# torque_sensor.net
KiCad netlist of a schematic drawn in EAGLE
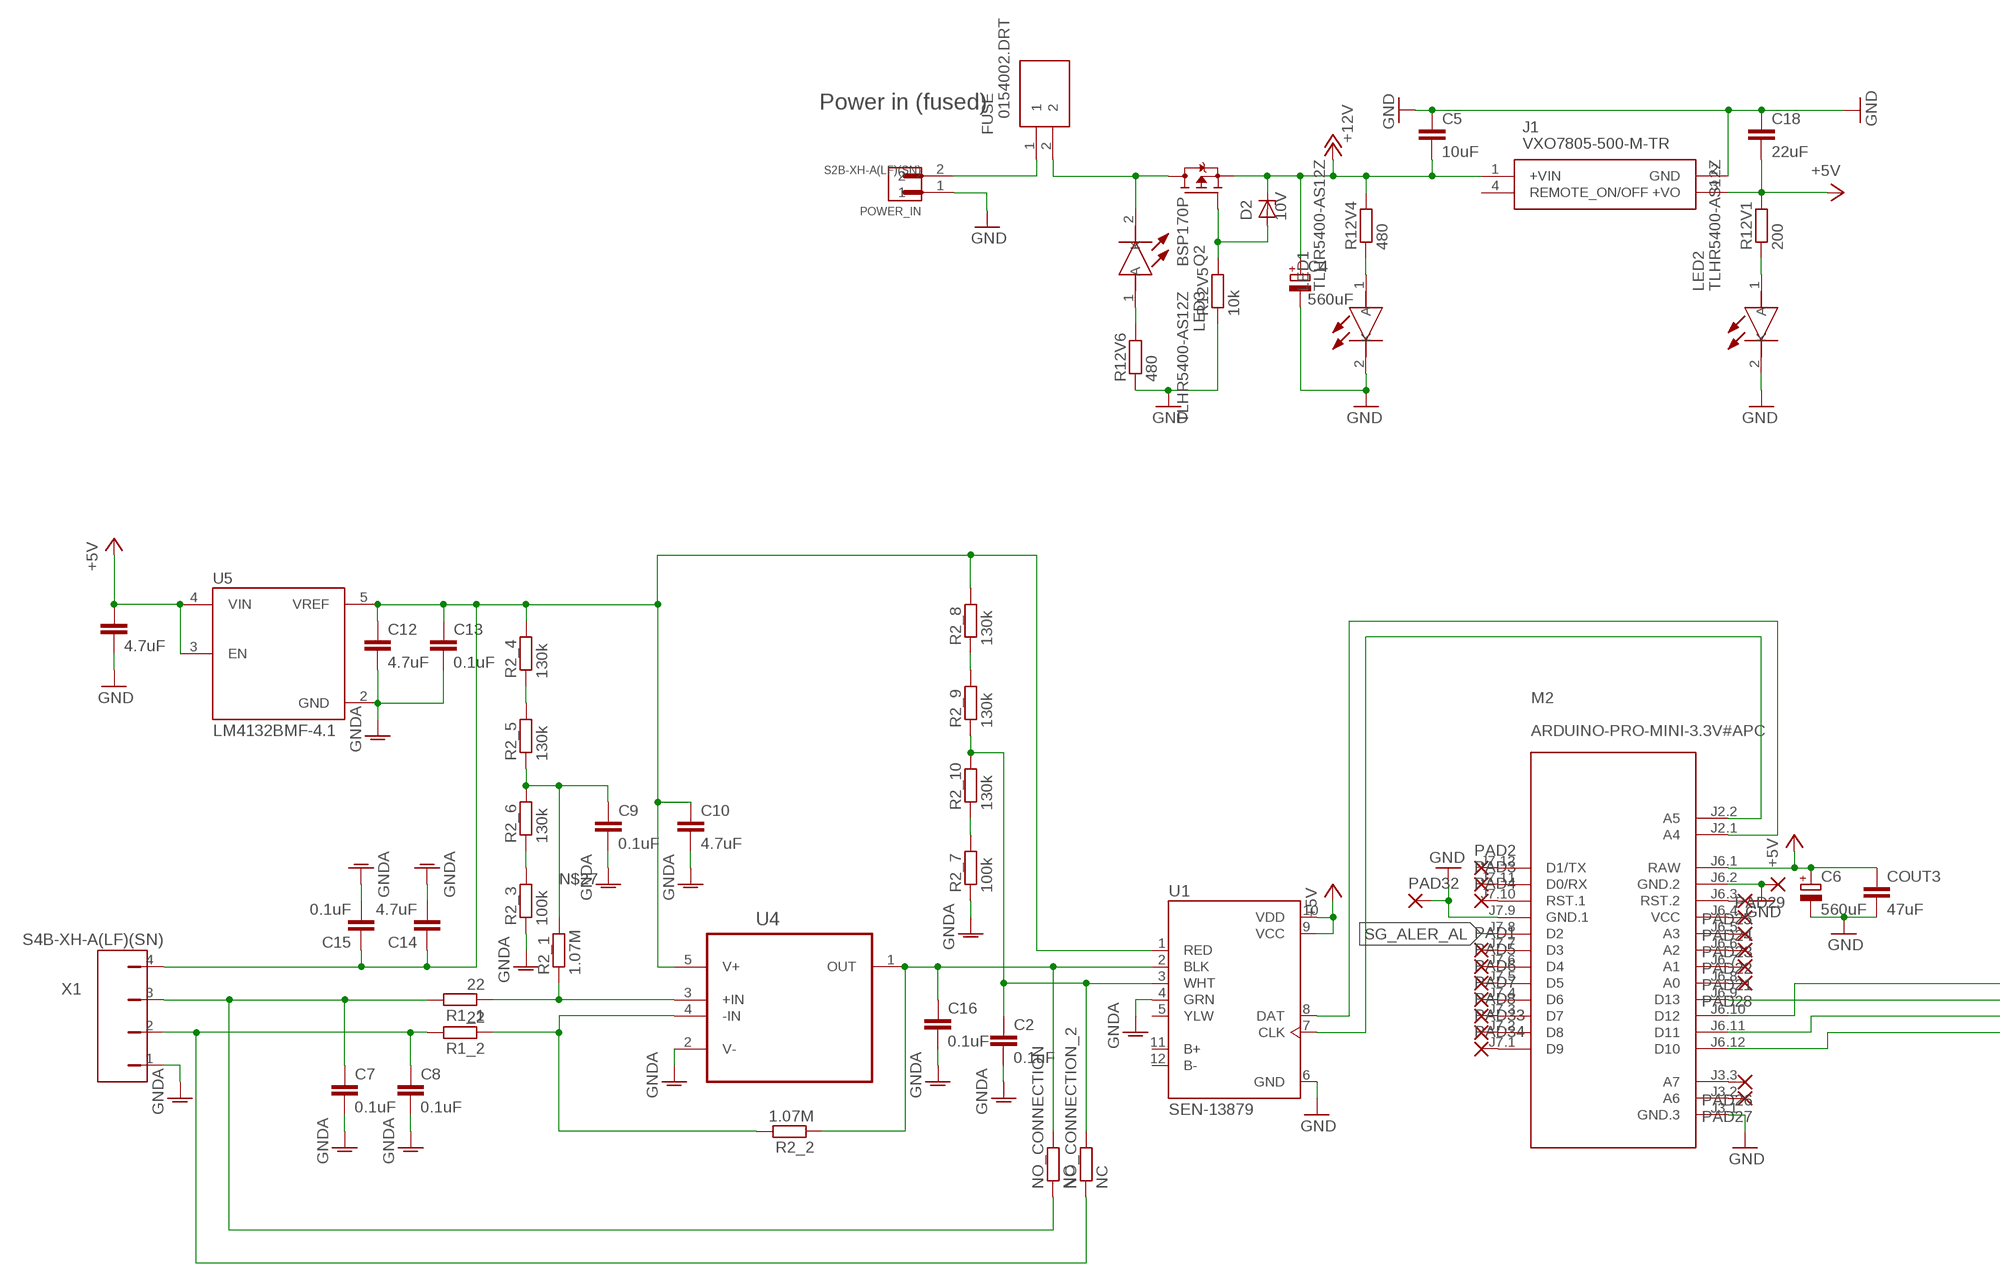
[diagram p0: schematic, sheet 1, part 1 of 2]
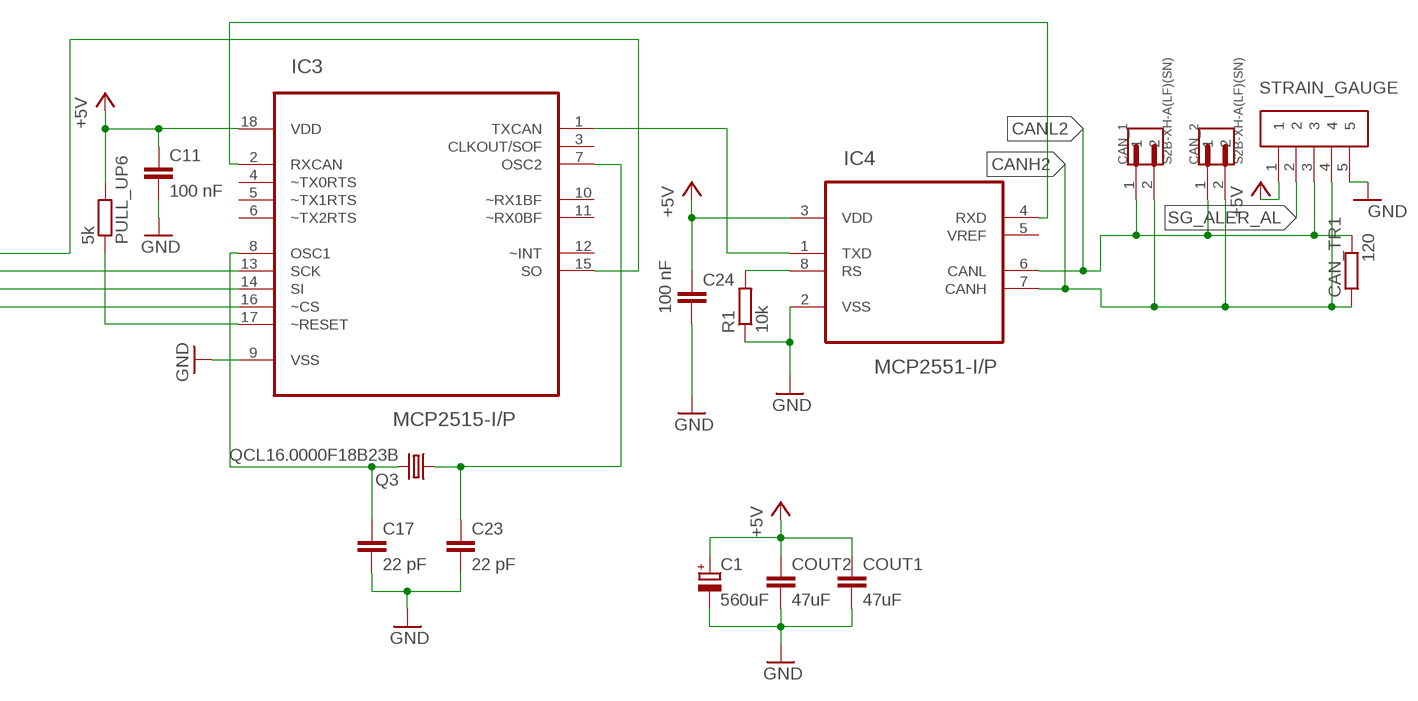
[diagram p1: schematic, sheet 1, part 2 of 2]

(export (version "E")
  (design (tool "Eeschema 10.0.6"))
  (components
    (comp (ref "C1")
      (value "560uF")
      (footprint "eagle-import:PANASONIC_F")
      (libsource (lib "eagle-import") (part "CPOL-EUF"))
    )
    (comp (ref "C2")
      (value "0.1uF")
      (footprint "eagle-import:C0805")
      (libsource (lib "eagle-import") (part "C-EUC0805"))
    )
    (comp (ref "C3")
      (value "4.7uF")
      (footprint "eagle-import:C0805")
      (libsource (lib "eagle-import") (part "C-EUC0805"))
    )
    (comp (ref "C4")
      (value "560uF")
      (footprint "eagle-import:PANASONIC_F")
      (libsource (lib "eagle-import") (part "CPOL-EUF"))
    )
    (comp (ref "C5")
      (value "10uF")
      (footprint "eagle-import:C0805")
      (libsource (lib "eagle-import") (part "C-EUC0805"))
    )
    (comp (ref "C6")
      (value "560uF")
      (footprint "eagle-import:PANASONIC_F")
      (libsource (lib "eagle-import") (part "CPOL-EUF"))
    )
    (comp (ref "C7")
      (value "0.1uF")
      (footprint "eagle-import:C0805")
      (libsource (lib "eagle-import") (part "C-EUC0805"))
    )
    (comp (ref "C8")
      (value "0.1uF")
      (footprint "eagle-import:C0805")
      (libsource (lib "eagle-import") (part "C-EUC0805"))
    )
    (comp (ref "C9")
      (value "0.1uF")
      (footprint "eagle-import:C0805")
      (libsource (lib "eagle-import") (part "C-EUC0805"))
    )
    (comp (ref "C10")
      (value "4.7uF")
      (footprint "eagle-import:C0805")
      (libsource (lib "eagle-import") (part "C-EUC0805"))
    )
    (comp (ref "C11")
      (value "100 nF")
      (footprint "eagle-import:C0805")
      (libsource (lib "eagle-import") (part "C-EUC0805"))
    )
    (comp (ref "C12")
      (value "4.7uF")
      (footprint "eagle-import:C0805")
      (libsource (lib "eagle-import") (part "C-EUC0805"))
    )
    (comp (ref "C13")
      (value "0.1uF")
      (footprint "eagle-import:C0805")
      (libsource (lib "eagle-import") (part "C-EUC0805"))
    )
    (comp (ref "C14")
      (value "4.7uF")
      (footprint "eagle-import:C0805")
      (libsource (lib "eagle-import") (part "C-EUC0805"))
    )
    (comp (ref "C15")
      (value "0.1uF")
      (footprint "eagle-import:C0805")
      (libsource (lib "eagle-import") (part "C-EUC0805"))
    )
    (comp (ref "C16")
      (value "0.1uF")
      (footprint "eagle-import:C0805")
      (libsource (lib "eagle-import") (part "C-EUC0805"))
    )
    (comp (ref "C17")
      (value "22 pF")
      (footprint "eagle-import:C0805")
      (libsource (lib "eagle-import") (part "C-EUC0805"))
    )
    (comp (ref "C18")
      (value "22uF")
      (footprint "eagle-import:C0805")
      (libsource (lib "eagle-import") (part "C-EUC0805"))
    )
    (comp (ref "C23")
      (value "22 pF")
      (footprint "eagle-import:C0805")
      (libsource (lib "eagle-import") (part "C-EUC0805"))
    )
    (comp (ref "C24")
      (value "100 nF")
      (footprint "eagle-import:C0805")
      (libsource (lib "eagle-import") (part "C-EUC0805"))
    )
    (comp (ref "CAN_1")
      (value "S2B-XH-A(LF)(SN)")
      (footprint "eagle-import:JST_S2B-XH-A(LF)(SN)")
      (fields
        (field (name "DIGI-KEY_PART_NUMBER") "455-2257-ND")
        (field (name "MF") "JST Sales")
        (field (name "MP") "S2B-XH-A_LF__SN_")
      )
      (libsource (lib "eagle-import") (part "S2B-XH-A(LF)(SN)"))
    )
    (comp (ref "CAN_2")
      (value "S2B-XH-A(LF)(SN)")
      (footprint "eagle-import:JST_S2B-XH-A(LF)(SN)")
      (fields
        (field (name "DIGI-KEY_PART_NUMBER") "455-2257-ND")
        (field (name "MF") "JST Sales")
        (field (name "MP") "S2B-XH-A_LF__SN_")
      )
      (libsource (lib "eagle-import") (part "S2B-XH-A(LF)(SN)"))
    )
    (comp (ref "CAN_TR1")
      (value "120")
      (footprint "eagle-import:R0805")
      (libsource (lib "eagle-import") (part "R-EU_R0805"))
    )
    (comp (ref "COUT1")
      (value "47uF")
      (footprint "eagle-import:C0805")
      (libsource (lib "eagle-import") (part "C-EUC0805"))
    )
    (comp (ref "COUT2")
      (value "47uF")
      (footprint "eagle-import:C0805")
      (libsource (lib "eagle-import") (part "C-EUC0805"))
    )
    (comp (ref "COUT3")
      (value "47uF")
      (footprint "eagle-import:C0805")
      (libsource (lib "eagle-import") (part "C-EUC0805"))
    )
    (comp (ref "D2")
      (value "10V")
      (footprint "eagle-import:SMB")
      (libsource (lib "eagle-import") (part "ZENER-DIODESMB"))
    )
    (comp (ref "FUSE")
      (value "0154002.DRT")
      (footprint "eagle-import:FUSM9750X381N")
      (fields (field (name "MOUSER_PART_NUMBER") "576-0154002.DRT"))
      (libsource (lib "eagle-import") (part "0154002.DRT"))
    )
    (comp (ref "IC3")
      (value "MCP2515-I/P")
      (footprint "eagle-import:DIP254P762X432-18")
      (fields (field (name "MF") "Microchip"))
      (libsource (lib "eagle-import") (part "MCP2515-I/P"))
    )
    (comp (ref "IC4")
      (value "MCP2551-I/P")
      (footprint "eagle-import:DIP254P762X432-8")
      (fields (field (name "MF") "Microchip"))
      (libsource (lib "eagle-import") (part "MCP2551-I/P"))
    )
    (comp (ref "J1")
      (value "VXO7805-500-M-TR")
      (footprint "eagle-import:VXO7805500MTR")
      (fields (field (name "MOUSER_PART_NUMBER") "490-VXO7805-500-M-TR"))
      (libsource (lib "eagle-import") (part "VXO7805-500-M-TR"))
    )
    (comp (ref "LED1")
      (value "TLHR5400-AS12Z")
      (footprint "eagle-import:TLHR5400AS12Z")
      (fields (field (name "MOUSER_PART_NUMBER") "78-TLHR5400-AS12Z"))
      (libsource (lib "eagle-import") (part "TLHR5400-AS12Z"))
    )
    (comp (ref "LED2")
      (value "TLHR5400-AS12Z")
      (footprint "eagle-import:TLHR5400AS12Z")
      (fields (field (name "MOUSER_PART_NUMBER") "78-TLHR5400-AS12Z"))
      (libsource (lib "eagle-import") (part "TLHR5400-AS12Z"))
    )
    (comp (ref "LED3")
      (value "TLHR5400-AS12Z")
      (footprint "eagle-import:TLHR5400AS12Z")
      (fields (field (name "MOUSER_PART_NUMBER") "78-TLHR5400-AS12Z"))
      (libsource (lib "eagle-import") (part "TLHR5400-AS12Z"))
    )
    (comp (ref "M2")
      (value "ARDUINO-PRO-MINI-3.3V#APC")
      (footprint "eagle-import:ARDUINO-PRO-MINI#APC")
      (libsource (lib "eagle-import") (part "ARDUINO-PRO-MINI-#APC3.3V"))
    )
    (comp (ref "NO_CONNECTION")
      (value "NC")
      (footprint "eagle-import:R0805")
      (libsource (lib "eagle-import") (part "R-EU_R0805"))
    )
    (comp (ref "NO_CONNECTION_2")
      (value "NC")
      (footprint "eagle-import:R0805")
      (libsource (lib "eagle-import") (part "R-EU_R0805"))
    )
    (comp (ref "PAD1")
      (value "SMD2")
      (footprint "eagle-import:SMD1,27-2,54")
      (libsource (lib "eagle-import") (part "SMD2"))
    )
    (comp (ref "PAD2")
      (value "SMD2")
      (footprint "eagle-import:SMD1,27-2,54")
      (libsource (lib "eagle-import") (part "SMD2"))
    )
    (comp (ref "PAD3")
      (value "SMD2")
      (footprint "eagle-import:SMD1,27-2,54")
      (libsource (lib "eagle-import") (part "SMD2"))
    )
    (comp (ref "PAD4")
      (value "SMD2")
      (footprint "eagle-import:SMD1,27-2,54")
      (libsource (lib "eagle-import") (part "SMD2"))
    )
    (comp (ref "PAD5")
      (value "SMD2")
      (footprint "eagle-import:SMD1,27-2,54")
      (libsource (lib "eagle-import") (part "SMD2"))
    )
    (comp (ref "PAD6")
      (value "SMD2")
      (footprint "eagle-import:SMD1,27-2,54")
      (libsource (lib "eagle-import") (part "SMD2"))
    )
    (comp (ref "PAD7")
      (value "SMD2")
      (footprint "eagle-import:SMD1,27-2,54")
      (libsource (lib "eagle-import") (part "SMD2"))
    )
    (comp (ref "PAD8")
      (value "SMD2")
      (footprint "eagle-import:SMD1,27-2,54")
      (libsource (lib "eagle-import") (part "SMD2"))
    )
    (comp (ref "PAD21")
      (value "SMD2")
      (footprint "eagle-import:SMD1,27-2,54")
      (libsource (lib "eagle-import") (part "SMD2"))
    )
    (comp (ref "PAD22")
      (value "SMD2")
      (footprint "eagle-import:SMD1,27-2,54")
      (libsource (lib "eagle-import") (part "SMD2"))
    )
    (comp (ref "PAD23")
      (value "SMD2")
      (footprint "eagle-import:SMD1,27-2,54")
      (libsource (lib "eagle-import") (part "SMD2"))
    )
    (comp (ref "PAD24")
      (value "SMD2")
      (footprint "eagle-import:SMD1,27-2,54")
      (libsource (lib "eagle-import") (part "SMD2"))
    )
    (comp (ref "PAD25")
      (value "SMD2")
      (footprint "eagle-import:SMD1,27-2,54")
      (libsource (lib "eagle-import") (part "SMD2"))
    )
    (comp (ref "PAD26")
      (value "SMD2")
      (footprint "eagle-import:SMD1,27-2,54")
      (libsource (lib "eagle-import") (part "SMD2"))
    )
    (comp (ref "PAD27")
      (value "SMD2")
      (footprint "eagle-import:SMD1,27-2,54")
      (libsource (lib "eagle-import") (part "SMD2"))
    )
    (comp (ref "PAD28")
      (value "SMD2")
      (footprint "eagle-import:SMD1,27-2,54")
      (libsource (lib "eagle-import") (part "SMD2"))
    )
    (comp (ref "PAD29")
      (value "SMD2")
      (footprint "eagle-import:SMD1,27-2,54")
      (libsource (lib "eagle-import") (part "SMD2"))
    )
    (comp (ref "PAD32")
      (value "SMD2")
      (footprint "eagle-import:SMD1,27-2,54")
      (libsource (lib "eagle-import") (part "SMD2"))
    )
    (comp (ref "PAD33")
      (value "SMD2")
      (footprint "eagle-import:SMD1,27-2,54")
      (libsource (lib "eagle-import") (part "SMD2"))
    )
    (comp (ref "PAD34")
      (value "SMD2")
      (footprint "eagle-import:SMD1,27-2,54")
      (libsource (lib "eagle-import") (part "SMD2"))
    )
    (comp (ref "POWER_IN")
      (value "S2B-XH-A(LF)(SN)")
      (footprint "eagle-import:JST_S2B-XH-A(LF)(SN)")
      (fields
        (field (name "DIGI-KEY_PART_NUMBER") "455-2257-ND")
        (field (name "MF") "JST Sales")
        (field (name "MP") "S2B-XH-A_LF__SN_")
      )
      (libsource (lib "eagle-import") (part "S2B-XH-A(LF)(SN)"))
    )
    (comp (ref "PULL_UP6")
      (value "5k")
      (footprint "eagle-import:R0805")
      (libsource (lib "eagle-import") (part "R-EU_R0805"))
    )
    (comp (ref "Q2")
      (value "BSP170P")
      (footprint "eagle-import:SOT223")
      (libsource (lib "eagle-import") (part "BSP170P"))
    )
    (comp (ref "Q3")
      (value "QCL16.0000F18B23B")
      (footprint "eagle-import:HC49_S")
      (libsource (lib "eagle-import") (part "CRYSTALHC49S"))
    )
    (comp (ref "R1")
      (value "10k")
      (footprint "eagle-import:R0805")
      (libsource (lib "eagle-import") (part "R-EU_R0805"))
    )
    (comp (ref "R1_1")
      (value "22")
      (footprint "eagle-import:R0805")
      (libsource (lib "eagle-import") (part "R-EU_R0805"))
    )
    (comp (ref "R1_2")
      (value "22")
      (footprint "eagle-import:R0805")
      (libsource (lib "eagle-import") (part "R-EU_R0805"))
    )
    (comp (ref "R2_1")
      (value "1.07M")
      (footprint "eagle-import:R0805")
      (libsource (lib "eagle-import") (part "R-EU_R0805"))
    )
    (comp (ref "R2_2")
      (value "1.07M")
      (footprint "eagle-import:R0805")
      (libsource (lib "eagle-import") (part "R-EU_R0805"))
    )
    (comp (ref "R2_3")
      (value "100k")
      (footprint "eagle-import:R0805")
      (libsource (lib "eagle-import") (part "R-EU_R0805"))
    )
    (comp (ref "R2_4")
      (value "130k")
      (footprint "eagle-import:R0805")
      (libsource (lib "eagle-import") (part "R-EU_R0805"))
    )
    (comp (ref "R2_5")
      (value "130k")
      (footprint "eagle-import:R0805")
      (libsource (lib "eagle-import") (part "R-EU_R0805"))
    )
    (comp (ref "R2_6")
      (value "130k")
      (footprint "eagle-import:R0805")
      (libsource (lib "eagle-import") (part "R-EU_R0805"))
    )
    (comp (ref "R2_7")
      (value "100k")
      (footprint "eagle-import:R0805")
      (libsource (lib "eagle-import") (part "R-EU_R0805"))
    )
    (comp (ref "R2_8")
      (value "130k")
      (footprint "eagle-import:R0805")
      (libsource (lib "eagle-import") (part "R-EU_R0805"))
    )
    (comp (ref "R2_9")
      (value "130k")
      (footprint "eagle-import:R0805")
      (libsource (lib "eagle-import") (part "R-EU_R0805"))
    )
    (comp (ref "R2_10")
      (value "130k")
      (footprint "eagle-import:R0805")
      (libsource (lib "eagle-import") (part "R-EU_R0805"))
    )
    (comp (ref "R12V1")
      (value "200")
      (footprint "eagle-import:R0805")
      (libsource (lib "eagle-import") (part "R-EU_R0805"))
    )
    (comp (ref "R12V4")
      (value "480")
      (footprint "eagle-import:R0805")
      (libsource (lib "eagle-import") (part "R-EU_R0805"))
    )
    (comp (ref "R12V5")
      (value "10k")
      (footprint "eagle-import:R0805")
      (libsource (lib "eagle-import") (part "R-EU_R0805"))
    )
    (comp (ref "R12V6")
      (value "480")
      (footprint "eagle-import:R0805")
      (libsource (lib "eagle-import") (part "R-EU_R0805"))
    )
    (comp (ref "STRAIN_GAUGE")
      (value "S5B-XH-A(LF)(SN)")
      (footprint "eagle-import:JST_S5B-XH-A(LF)(SN)")
      (fields (field (name "MF") "JST Sales") (field (name "MP") "S5B-XH-A_LF__SN_"))
      (libsource (lib "eagle-import") (part "S5B-XH-A(LF)(SN)"))
    )
    (comp (ref "U1")
      (value "SEN-13879")
      (footprint "eagle-import:SPARKFUN_SEN-13879")
      (fields (field (name "DIGI-KEY_PART_NUMBER") "1568-1436-ND") (field (name "MF") "SparkFun"))
      (libsource (lib "eagle-import") (part "SEN-13879"))
    )
    (comp (ref "U4")
      (value "LMP7731MF")
      (footprint "eagle-import:SOT95P284X119-5N")
      (fields (field (name "MF") "Texas Instruments"))
      (libsource (lib "eagle-import") (part "LMP7731MF"))
    )
    (comp (ref "U5")
      (value "LM4132BMF-4.1")
      (footprint "eagle-import:SOT95P280X145-5N")
      (fields (field (name "MF") "Texas Instruments"))
      (libsource (lib "eagle-import") (part "LM4132BMF-4.1"))
    )
    (comp (ref "X1")
      (value "S4B-XH-A(LF)(SN)")
      (footprint "eagle-import:S4B-XH-A(LF)(SN)")
      (fields (field (name "MF") "JST Sales") (field (name "MP") "S4B-XH-A_LF__SN_"))
      (libsource (lib "eagle-import") (part "S4B-XH-A(LF)(SN)"))
    )
  )
  (nets
    (net (code "1") (name "+5V") (class "Default")
      (node (ref "C1") (pin "+") (pinfunction "+_+") (pintype "passive"))
      (node (ref "C11") (pin "1") (pinfunction "1_1") (pintype "passive"))
      (node (ref "C18") (pin "2") (pinfunction "2_2") (pintype "passive"))
      (node (ref "C24") (pin "1") (pinfunction "1_1") (pintype "passive"))
      (node (ref "C3") (pin "1") (pinfunction "1_1") (pintype "passive"))
      (node (ref "C6") (pin "+") (pinfunction "+_+") (pintype "passive"))
      (node (ref "COUT1") (pin "1") (pinfunction "1_1") (pintype "passive"))
      (node (ref "COUT2") (pin "1") (pinfunction "1_1") (pintype "passive"))
      (node (ref "COUT3") (pin "1") (pinfunction "1_1") (pintype "passive"))
      (node (ref "IC3") (pin "18") (pinfunction "VDD_18") (pintype "power_in"))
      (node (ref "IC4") (pin "3") (pinfunction "VDD_3") (pintype "power_in"))
      (node (ref "J1") (pin "3") (pinfunction "+VO_3") (pintype "bidirectional"))
      (node (ref "M2") (pin "J6.1") (pinfunction "RAW_J6.1") (pintype "power_in"))
      (node (ref "PULL_UP6") (pin "2") (pinfunction "2_2") (pintype "passive"))
      (node (ref "R12V1") (pin "2") (pinfunction "2_2") (pintype "passive"))
      (node (ref "STRAIN_GAUGE") (pin "1") (pinfunction "1_1") (pintype "passive"))
      (node (ref "U1") (pin "10") (pinfunction "VDD_10") (pintype "power_in"))
      (node (ref "U1") (pin "9") (pinfunction "VCC_9") (pintype "power_in"))
      (node (ref "U5") (pin "3") (pinfunction "EN_3") (pintype "input"))
      (node (ref "U5") (pin "4") (pinfunction "VIN_4") (pintype "power_in"))
    )
    (net (code "2") (name "+12V") (class "Default")
      (node (ref "C4") (pin "+") (pinfunction "+_+") (pintype "passive"))
      (node (ref "C5") (pin "2") (pinfunction "2_2") (pintype "passive"))
      (node (ref "D2") (pin "C") (pinfunction "C_C") (pintype "passive"))
      (node (ref "J1") (pin "1") (pinfunction "+VIN_1") (pintype "bidirectional"))
      (node (ref "Q2") (pin "3") (pinfunction "S_3") (pintype "passive"))
      (node (ref "R12V4") (pin "2") (pinfunction "2_2") (pintype "passive"))
    )
    (net (code "3") (name "/N$27") (class "Default")
      (node (ref "C9") (pin "1") (pinfunction "1_1") (pintype "passive"))
      (node (ref "R2_1") (pin "2") (pinfunction "2_2") (pintype "passive"))
      (node (ref "R2_5") (pin "1") (pinfunction "1_1") (pintype "passive"))
      (node (ref "R2_6") (pin "2") (pinfunction "2_2") (pintype "passive"))
    )
    (net (code "4") (name "CANH2") (class "Default")
      (node (ref "CAN_1") (pin "2") (pinfunction "2_2") (pintype "passive"))
      (node (ref "CAN_2") (pin "2") (pinfunction "2_2") (pintype "passive"))
      (node (ref "CAN_TR1") (pin "1") (pinfunction "1_1") (pintype "passive"))
      (node (ref "IC4") (pin "7") (pinfunction "CANH_7") (pintype "bidirectional"))
      (node (ref "STRAIN_GAUGE") (pin "4") (pinfunction "4_4") (pintype "passive"))
    )
    (net (code "5") (name "CANL2") (class "Default")
      (node (ref "CAN_1") (pin "1") (pinfunction "1_1") (pintype "passive"))
      (node (ref "CAN_2") (pin "1") (pinfunction "1_1") (pintype "passive"))
      (node (ref "CAN_TR1") (pin "2") (pinfunction "2_2") (pintype "passive"))
      (node (ref "IC4") (pin "6") (pinfunction "CANL_6") (pintype "bidirectional"))
      (node (ref "STRAIN_GAUGE") (pin "3") (pinfunction "3_3") (pintype "passive"))
    )
    (net (code "6") (name "GND") (class "Default")
      (node (ref "C1") (pin "-") (pinfunction "-_-") (pintype "passive"))
      (node (ref "C11") (pin "2") (pinfunction "2_2") (pintype "passive"))
      (node (ref "C17") (pin "2") (pinfunction "2_2") (pintype "passive"))
      (node (ref "C18") (pin "1") (pinfunction "1_1") (pintype "passive"))
      (node (ref "C23") (pin "2") (pinfunction "2_2") (pintype "passive"))
      (node (ref "C24") (pin "2") (pinfunction "2_2") (pintype "passive"))
      (node (ref "C3") (pin "2") (pinfunction "2_2") (pintype "passive"))
      (node (ref "C4") (pin "-") (pinfunction "-_-") (pintype "passive"))
      (node (ref "C5") (pin "1") (pinfunction "1_1") (pintype "passive"))
      (node (ref "C6") (pin "-") (pinfunction "-_-") (pintype "passive"))
      (node (ref "COUT1") (pin "2") (pinfunction "2_2") (pintype "passive"))
      (node (ref "COUT2") (pin "2") (pinfunction "2_2") (pintype "passive"))
      (node (ref "COUT3") (pin "2") (pinfunction "2_2") (pintype "passive"))
      (node (ref "IC3") (pin "9") (pinfunction "VSS_9") (pintype "power_in"))
      (node (ref "IC4") (pin "2") (pinfunction "VSS_2") (pintype "power_in"))
      (node (ref "J1") (pin "2") (pinfunction "GND_2") (pintype "bidirectional"))
      (node (ref "LED1") (pin "2") (pinfunction "K_2") (pintype "bidirectional"))
      (node (ref "LED2") (pin "2") (pinfunction "K_2") (pintype "bidirectional"))
      (node (ref "M2") (pin "J3.1") (pinfunction "GND.3_J3.1") (pintype "bidirectional"))
      (node (ref "M2") (pin "J6.2") (pinfunction "GND.2_J6.2") (pintype "power_in"))
      (node (ref "M2") (pin "J7.9") (pinfunction "GND.1_J7.9") (pintype "power_in"))
      (node (ref "PAD29") (pin "1") (pinfunction "P_1") (pintype "passive"))
      (node (ref "PAD32") (pin "1") (pinfunction "P_1") (pintype "passive"))
      (node (ref "POWER_IN") (pin "1") (pinfunction "1_1") (pintype "passive"))
      (node (ref "R1") (pin "1") (pinfunction "1_1") (pintype "passive"))
      (node (ref "R12V5") (pin "1") (pinfunction "1_1") (pintype "passive"))
      (node (ref "R12V6") (pin "1") (pinfunction "1_1") (pintype "passive"))
      (node (ref "STRAIN_GAUGE") (pin "5") (pinfunction "5_5") (pintype "passive"))
      (node (ref "U1") (pin "6") (pinfunction "GND_6") (pintype "power_in"))
    )
    (net (code "7") (name "GNDA") (class "Default")
      (node (ref "C10") (pin "2") (pinfunction "2_2") (pintype "passive"))
      (node (ref "C12") (pin "2") (pinfunction "2_2") (pintype "passive"))
      (node (ref "C13") (pin "2") (pinfunction "2_2") (pintype "passive"))
      (node (ref "C14") (pin "2") (pinfunction "2_2") (pintype "passive"))
      (node (ref "C15") (pin "2") (pinfunction "2_2") (pintype "passive"))
      (node (ref "C16") (pin "2") (pinfunction "2_2") (pintype "passive"))
      (node (ref "C2") (pin "2") (pinfunction "2_2") (pintype "passive"))
      (node (ref "C7") (pin "2") (pinfunction "2_2") (pintype "passive"))
      (node (ref "C8") (pin "2") (pinfunction "2_2") (pintype "passive"))
      (node (ref "C9") (pin "2") (pinfunction "2_2") (pintype "passive"))
      (node (ref "R2_3") (pin "1") (pinfunction "1_1") (pintype "passive"))
      (node (ref "R2_7") (pin "1") (pinfunction "1_1") (pintype "passive"))
      (node (ref "U1") (pin "4") (pinfunction "GRN_4") (pintype "input"))
      (node (ref "U4") (pin "2") (pinfunction "V-_2") (pintype "power_in"))
      (node (ref "U5") (pin "2") (pinfunction "GND_2") (pintype "power_in"))
      (node (ref "X1") (pin "1") (pinfunction "1_1") (pintype "passive"))
    )
    (net (code "8") (name "Net-(C7-Pad1)") (class "Default")
      (node (ref "C7") (pin "1") (pinfunction "1_1") (pintype "passive"))
      (node (ref "NO_CONNECTION") (pin "1") (pinfunction "1_1") (pintype "passive"))
      (node (ref "R1_1") (pin "2") (pinfunction "2_2") (pintype "passive"))
      (node (ref "X1") (pin "3") (pinfunction "3_3") (pintype "passive"))
    )
    (net (code "9") (name "Net-(C8-Pad1)") (class "Default")
      (node (ref "C8") (pin "1") (pinfunction "1_1") (pintype "passive"))
      (node (ref "NO_CONNECTION_2") (pin "1") (pinfunction "1_1") (pintype "passive"))
      (node (ref "R1_2") (pin "2") (pinfunction "2_2") (pintype "passive"))
      (node (ref "X1") (pin "2") (pinfunction "2_2") (pintype "passive"))
    )
    (net (code "10") (name "Net-(FUSE-Pad1)") (class "Default")
      (node (ref "FUSE") (pin "1") (pinfunction "1_1") (pintype "bidirectional"))
      (node (ref "POWER_IN") (pin "2") (pinfunction "2_2") (pintype "passive"))
    )
    (net (code "11") (name "Net-(IC3-OSC1)") (class "Default")
      (node (ref "C17") (pin "1") (pinfunction "1_1") (pintype "passive"))
      (node (ref "IC3") (pin "8") (pinfunction "OSC1_8") (pintype "input"))
      (node (ref "Q3") (pin "2") (pinfunction "2_2") (pintype "passive"))
    )
    (net (code "12") (name "Net-(IC3-OSC2)") (class "Default")
      (node (ref "C23") (pin "1") (pinfunction "1_1") (pintype "passive"))
      (node (ref "IC3") (pin "7") (pinfunction "OSC2_7") (pintype "output"))
      (node (ref "Q3") (pin "1") (pinfunction "1_1") (pintype "passive"))
    )
    (net (code "13") (name "Net-(IC3-RXCAN)") (class "Default")
      (node (ref "IC3") (pin "2") (pinfunction "RXCAN_2") (pintype "input"))
      (node (ref "IC4") (pin "4") (pinfunction "RXD_4") (pintype "output"))
    )
    (net (code "14") (name "Net-(IC3-SCK)") (class "Default")
      (node (ref "IC3") (pin "13") (pinfunction "SCK_13") (pintype "input"))
      (node (ref "M2") (pin "J6.9") (pinfunction "D13_J6.9") (pintype "bidirectional"))
    )
    (net (code "15") (name "Net-(IC3-SI)") (class "Default")
      (node (ref "IC3") (pin "14") (pinfunction "SI_14") (pintype "input"))
      (node (ref "M2") (pin "J6.11") (pinfunction "D11_J6.11") (pintype "bidirectional"))
    )
    (net (code "16") (name "Net-(IC3-SO)") (class "Default")
      (node (ref "IC3") (pin "15") (pinfunction "SO_15") (pintype "output"))
      (node (ref "M2") (pin "J6.10") (pinfunction "D12_J6.10") (pintype "bidirectional"))
    )
    (net (code "17") (name "Net-(IC3-TXCAN)") (class "Default")
      (node (ref "IC3") (pin "1") (pinfunction "TXCAN_1") (pintype "output"))
      (node (ref "IC4") (pin "1") (pinfunction "TXD_1") (pintype "input"))
    )
    (net (code "18") (name "Net-(IC3-~{CS})") (class "Default")
      (node (ref "IC3") (pin "16") (pinfunction "~{CS}_16") (pintype "input"))
      (node (ref "M2") (pin "J6.12") (pinfunction "D10_J6.12") (pintype "bidirectional"))
    )
    (net (code "19") (name "Net-(IC3-~{RESET})") (class "Default")
      (node (ref "IC3") (pin "17") (pinfunction "~{RESET}_17") (pintype "input"))
      (node (ref "PULL_UP6") (pin "1") (pinfunction "1_1") (pintype "passive"))
    )
    (net (code "20") (name "Net-(IC4-RS)") (class "Default")
      (node (ref "IC4") (pin "8") (pinfunction "RS_8") (pintype "input"))
      (node (ref "R1") (pin "2") (pinfunction "2_2") (pintype "passive"))
    )
    (net (code "21") (name "Net-(LED1-A)") (class "Default")
      (node (ref "LED1") (pin "1") (pinfunction "A_1") (pintype "bidirectional"))
      (node (ref "R12V4") (pin "1") (pinfunction "1_1") (pintype "passive"))
    )
    (net (code "22") (name "Net-(LED2-A)") (class "Default")
      (node (ref "LED2") (pin "1") (pinfunction "A_1") (pintype "bidirectional"))
      (node (ref "R12V1") (pin "1") (pinfunction "1_1") (pintype "passive"))
    )
    (net (code "23") (name "Net-(LED3-A)") (class "Default")
      (node (ref "LED3") (pin "1") (pinfunction "A_1") (pintype "bidirectional"))
      (node (ref "R12V6") (pin "2") (pinfunction "2_2") (pintype "passive"))
    )
    (net (code "24") (name "Net-(LED3-K)") (class "Default")
      (node (ref "FUSE") (pin "2") (pinfunction "2_2") (pintype "bidirectional"))
      (node (ref "LED3") (pin "2") (pinfunction "K_2") (pintype "bidirectional"))
      (node (ref "Q2") (pin "2") (pinfunction "D_2") (pintype "passive"))
      (node (ref "Q2") (pin "4") (pinfunction "D_4") (pintype "passive"))
    )
    (net (code "25") (name "Net-(M2-A0)") (class "Default")
      (node (ref "M2") (pin "J6.8") (pinfunction "A0_J6.8") (pintype "bidirectional"))
      (node (ref "PAD28") (pin "1") (pinfunction "P_1") (pintype "passive"))
    )
    (net (code "26") (name "Net-(M2-A1)") (class "Default")
      (node (ref "M2") (pin "J6.7") (pinfunction "A1_J6.7") (pintype "bidirectional"))
      (node (ref "PAD21") (pin "1") (pinfunction "P_1") (pintype "passive"))
    )
    (net (code "27") (name "Net-(M2-A2)") (class "Default")
      (node (ref "M2") (pin "J6.6") (pinfunction "A2_J6.6") (pintype "bidirectional"))
      (node (ref "PAD22") (pin "1") (pinfunction "P_1") (pintype "passive"))
    )
    (net (code "28") (name "Net-(M2-A3)") (class "Default")
      (node (ref "M2") (pin "J6.5") (pinfunction "A3_J6.5") (pintype "bidirectional"))
      (node (ref "PAD23") (pin "1") (pinfunction "P_1") (pintype "passive"))
    )
    (net (code "29") (name "Net-(M2-A4)") (class "Default")
      (node (ref "M2") (pin "J2.1") (pinfunction "A4_J2.1") (pintype "bidirectional"))
      (node (ref "U1") (pin "8") (pinfunction "DAT_8") (pintype "output"))
    )
    (net (code "30") (name "Net-(M2-A5)") (class "Default")
      (node (ref "M2") (pin "J2.2") (pinfunction "A5_J2.2") (pintype "bidirectional"))
      (node (ref "U1") (pin "7") (pinfunction "CLK_7") (pintype "input"))
    )
    (net (code "31") (name "Net-(M2-A6)") (class "Default")
      (node (ref "M2") (pin "J3.2") (pinfunction "A6_J3.2") (pintype "bidirectional"))
      (node (ref "PAD27") (pin "1") (pinfunction "P_1") (pintype "passive"))
    )
    (net (code "32") (name "Net-(M2-A7)") (class "Default")
      (node (ref "M2") (pin "J3.3") (pinfunction "A7_J3.3") (pintype "bidirectional"))
      (node (ref "PAD26") (pin "1") (pinfunction "P_1") (pintype "passive"))
    )
    (net (code "33") (name "Net-(M2-D0{slash}RX)") (class "Default")
      (node (ref "M2") (pin "J7.11") (pinfunction "D0/RX_J7.11") (pintype "bidirectional"))
      (node (ref "PAD3") (pin "1") (pinfunction "P_1") (pintype "passive"))
    )
    (net (code "34") (name "Net-(M2-D1{slash}TX)") (class "Default")
      (node (ref "M2") (pin "J7.12") (pinfunction "D1/TX_J7.12") (pintype "bidirectional"))
      (node (ref "PAD2") (pin "1") (pinfunction "P_1") (pintype "passive"))
    )
    (net (code "35") (name "Net-(M2-D3)") (class "Default")
      (node (ref "M2") (pin "J7.7") (pinfunction "D3_J7.7") (pintype "bidirectional"))
      (node (ref "PAD1") (pin "1") (pinfunction "P_1") (pintype "passive"))
    )
    (net (code "36") (name "Net-(M2-D4)") (class "Default")
      (node (ref "M2") (pin "J7.6") (pinfunction "D4_J7.6") (pintype "bidirectional"))
      (node (ref "PAD5") (pin "1") (pinfunction "P_1") (pintype "passive"))
    )
    (net (code "37") (name "Net-(M2-D5)") (class "Default")
      (node (ref "M2") (pin "J7.5") (pinfunction "D5_J7.5") (pintype "bidirectional"))
      (node (ref "PAD6") (pin "1") (pinfunction "P_1") (pintype "passive"))
    )
    (net (code "38") (name "Net-(M2-D6)") (class "Default")
      (node (ref "M2") (pin "J7.4") (pinfunction "D6_J7.4") (pintype "bidirectional"))
      (node (ref "PAD7") (pin "1") (pinfunction "P_1") (pintype "passive"))
    )
    (net (code "39") (name "Net-(M2-D7)") (class "Default")
      (node (ref "M2") (pin "J7.3") (pinfunction "D7_J7.3") (pintype "bidirectional"))
      (node (ref "PAD8") (pin "1") (pinfunction "P_1") (pintype "passive"))
    )
    (net (code "40") (name "Net-(M2-D8)") (class "Default")
      (node (ref "M2") (pin "J7.2") (pinfunction "D8_J7.2") (pintype "bidirectional"))
      (node (ref "PAD33") (pin "1") (pinfunction "P_1") (pintype "passive"))
    )
    (net (code "41") (name "Net-(M2-D9)") (class "Default")
      (node (ref "M2") (pin "J7.1") (pinfunction "D9_J7.1") (pintype "bidirectional"))
      (node (ref "PAD34") (pin "1") (pinfunction "P_1") (pintype "passive"))
    )
    (net (code "42") (name "Net-(M2-RST.1)") (class "Default")
      (node (ref "M2") (pin "J7.10") (pinfunction "RST.1_J7.10") (pintype "bidirectional"))
      (node (ref "PAD4") (pin "1") (pinfunction "P_1") (pintype "passive"))
    )
    (net (code "43") (name "Net-(M2-RST.2)") (class "Default")
      (node (ref "M2") (pin "J6.3") (pinfunction "RST.2_J6.3") (pintype "bidirectional"))
      (node (ref "PAD25") (pin "1") (pinfunction "P_1") (pintype "passive"))
    )
    (net (code "44") (name "Net-(M2-VCC)") (class "Default")
      (node (ref "M2") (pin "J6.4") (pinfunction "VCC_J6.4") (pintype "power_in"))
      (node (ref "PAD24") (pin "1") (pinfunction "P_1") (pintype "passive"))
    )
    (net (code "45") (name "Net-(Q2-G)") (class "Default")
      (node (ref "D2") (pin "A") (pinfunction "A_A") (pintype "passive"))
      (node (ref "Q2") (pin "1") (pinfunction "G_1") (pintype "passive"))
      (node (ref "R12V5") (pin "2") (pinfunction "2_2") (pintype "passive"))
    )
    (net (code "46") (name "Net-(R2_3-Pad2)") (class "Default")
      (node (ref "R2_3") (pin "2") (pinfunction "2_2") (pintype "passive"))
      (node (ref "R2_6") (pin "1") (pinfunction "1_1") (pintype "passive"))
    )
    (net (code "47") (name "Net-(R2_4-Pad1)") (class "Default")
      (node (ref "R2_4") (pin "1") (pinfunction "1_1") (pintype "passive"))
      (node (ref "R2_5") (pin "2") (pinfunction "2_2") (pintype "passive"))
    )
    (net (code "48") (name "Net-(R2_8-Pad1)") (class "Default")
      (node (ref "R2_8") (pin "1") (pinfunction "1_1") (pintype "passive"))
      (node (ref "R2_9") (pin "2") (pinfunction "2_2") (pintype "passive"))
    )
    (net (code "49") (name "Net-(R2_10-Pad1)") (class "Default")
      (node (ref "R2_10") (pin "1") (pinfunction "1_1") (pintype "passive"))
      (node (ref "R2_7") (pin "2") (pinfunction "2_2") (pintype "passive"))
    )
    (net (code "50") (name "Net-(U1-BLK)") (class "Default")
      (node (ref "C16") (pin "1") (pinfunction "1_1") (pintype "passive"))
      (node (ref "NO_CONNECTION") (pin "2") (pinfunction "2_2") (pintype "passive"))
      (node (ref "R2_2") (pin "1") (pinfunction "1_1") (pintype "passive"))
      (node (ref "U1") (pin "2") (pinfunction "BLK_2") (pintype "bidirectional"))
      (node (ref "U4") (pin "1") (pinfunction "OUT_1") (pintype "output"))
    )
    (net (code "51") (name "Net-(U1-RED)") (class "Default")
      (node (ref "C10") (pin "1") (pinfunction "1_1") (pintype "passive"))
      (node (ref "C12") (pin "1") (pinfunction "1_1") (pintype "passive"))
      (node (ref "C13") (pin "1") (pinfunction "1_1") (pintype "passive"))
      (node (ref "C14") (pin "1") (pinfunction "1_1") (pintype "passive"))
      (node (ref "C15") (pin "1") (pinfunction "1_1") (pintype "passive"))
      (node (ref "R2_4") (pin "2") (pinfunction "2_2") (pintype "passive"))
      (node (ref "R2_8") (pin "2") (pinfunction "2_2") (pintype "passive"))
      (node (ref "U1") (pin "1") (pinfunction "RED_1") (pintype "bidirectional"))
      (node (ref "U4") (pin "5") (pinfunction "V+_5") (pintype "power_in"))
      (node (ref "U5") (pin "5") (pinfunction "VREF_5") (pintype "power_in"))
      (node (ref "X1") (pin "4") (pinfunction "4_4") (pintype "passive"))
    )
    (net (code "52") (name "Net-(U1-WHT)") (class "Default")
      (node (ref "C2") (pin "1") (pinfunction "1_1") (pintype "passive"))
      (node (ref "NO_CONNECTION_2") (pin "2") (pinfunction "2_2") (pintype "passive"))
      (node (ref "R2_10") (pin "2") (pinfunction "2_2") (pintype "passive"))
      (node (ref "R2_9") (pin "1") (pinfunction "1_1") (pintype "passive"))
      (node (ref "U1") (pin "3") (pinfunction "WHT_3") (pintype "input"))
    )
    (net (code "53") (name "Net-(U4-+IN)") (class "Default")
      (node (ref "R1_1") (pin "1") (pinfunction "1_1") (pintype "passive"))
      (node (ref "R2_1") (pin "1") (pinfunction "1_1") (pintype "passive"))
      (node (ref "U4") (pin "3") (pinfunction "+IN_3") (pintype "input"))
    )
    (net (code "54") (name "Net-(U4--IN)") (class "Default")
      (node (ref "R1_2") (pin "1") (pinfunction "1_1") (pintype "passive"))
      (node (ref "R2_2") (pin "2") (pinfunction "2_2") (pintype "passive"))
      (node (ref "U4") (pin "4") (pinfunction "-IN_4") (pintype "input"))
    )
    (net (code "55") (name "SG_ALER_AL") (class "Default")
      (node (ref "M2") (pin "J7.8") (pinfunction "D2_J7.8") (pintype "bidirectional"))
      (node (ref "STRAIN_GAUGE") (pin "2") (pinfunction "2_2") (pintype "passive"))
    )
    (net (code "56") (name "unconnected-(IC3-CLKOUT{slash}SOF-Pad3)") (class "Default")
      (node (ref "IC3") (pin "3") (pinfunction "CLKOUT/SOF_3") (pintype "output"))
    )
    (net (code "57") (name "unconnected-(IC3-~{INT}-Pad12)") (class "Default")
      (node (ref "IC3") (pin "12") (pinfunction "~{INT}_12") (pintype "output"))
    )
    (net (code "58") (name "unconnected-(IC3-~{RX0BF}-Pad11)") (class "Default")
      (node (ref "IC3") (pin "11") (pinfunction "~{RX0BF}_11") (pintype "output"))
    )
    (net (code "59") (name "unconnected-(IC3-~{RX1BF}-Pad10)") (class "Default")
      (node (ref "IC3") (pin "10") (pinfunction "~{RX1BF}_10") (pintype "output"))
    )
    (net (code "60") (name "unconnected-(IC3-~{TX0RTS}-Pad4)") (class "Default")
      (node (ref "IC3") (pin "4") (pinfunction "~{TX0RTS}_4") (pintype "input"))
    )
    (net (code "61") (name "unconnected-(IC3-~{TX1RTS}-Pad5)") (class "Default")
      (node (ref "IC3") (pin "5") (pinfunction "~{TX1RTS}_5") (pintype "input"))
    )
    (net (code "62") (name "unconnected-(IC3-~{TX2RTS}-Pad6)") (class "Default")
      (node (ref "IC3") (pin "6") (pinfunction "~{TX2RTS}_6") (pintype "input"))
    )
    (net (code "63") (name "unconnected-(IC4-VREF-Pad5)") (class "Default")
      (node (ref "IC4") (pin "5") (pinfunction "VREF_5") (pintype "output"))
    )
    (net (code "64") (name "unconnected-(J1-REMOTE_ON{slash}OFF-Pad4)") (class "Default")
      (node (ref "J1") (pin "4") (pinfunction "REMOTE_ON/OFF_4") (pintype "bidirectional"))
    )
    (net (code "65") (name "unconnected-(U1-B+-Pad11)") (class "Default")
      (node (ref "U1") (pin "11") (pinfunction "B+_11") (pintype "input"))
    )
    (net (code "66") (name "unconnected-(U1-B--Pad12)") (class "Default")
      (node (ref "U1") (pin "12") (pinfunction "B-_12") (pintype "input"))
    )
    (net (code "67") (name "unconnected-(U1-YLW-Pad5)") (class "Default")
      (node (ref "U1") (pin "5") (pinfunction "YLW_5") (pintype "bidirectional"))
    )
  )
)
